# Ports.net
KiCad netlist of a schematic drawn in Altium Designer
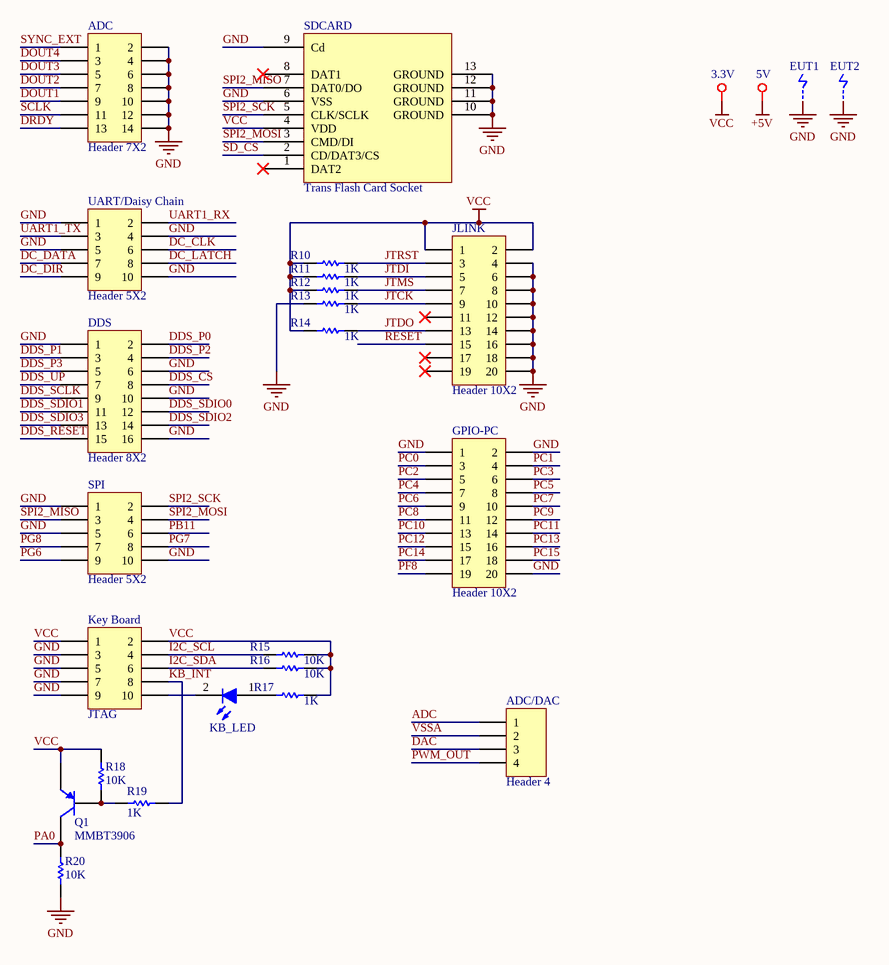
[diagram p0: Ports.SchDoc]

(export (version "E")
  (design (tool "Eeschema 10.0.6"))
  (components
    (comp (ref "3.3V")
      (value "TestPoint")
      (footprint "TestHole")
      (libsource (lib "Slivy's ibrary") (part "TestPoint"))
    )
    (comp (ref "5V")
      (value "TestPoint")
      (footprint "TestHole")
      (libsource (lib "Slivy's ibrary") (part "TestPoint"))
    )
    (comp (ref "ADC")
      (value "Header 7X2")
      (footprint "HEADER7X2")
      (description "Header, 7-Pin, Dual row")
      (fields (field (name "PUBLISHER") "Altium Limited"))
      (libsource (lib "Miscellaneous Connectors") (part "Header 7X2"))
    )
    (comp (ref "ADC/DAC")
      (value "Header 4")
      (footprint "HDR1X4")
      (description "Header, 4-Pin")
      (fields (field (name "PUBLISHER") "Altium Limited"))
      (libsource (lib "Miscellaneous Connectors") (part "Header 4"))
    )
    (comp (ref "DDS")
      (value "Header 8X2")
      (footprint "HEADER8X2")
      (description "Header, 8-Pin, Dual row")
      (fields (field (name "PUBLISHER") "Altium Limited"))
      (libsource (lib "Miscellaneous Connectors") (part "Header 8X2"))
    )
    (comp (ref "EUT1") (value "EUT") (footprint "EUT") (libsource (lib "Slivy's ibrary") (part "EUT")))
    (comp (ref "EUT2") (value "EUT") (footprint "EUT") (libsource (lib "Slivy's ibrary") (part "EUT")))
    (comp (ref "GPIO-PC")
      (value "Header 10X2")
      (footprint "HEADER 10X2")
      (description "Header, 10-Pin, Dual row")
      (fields (field (name "PUBLISHER") "Altium Limited"))
      (libsource (lib "Miscellaneous Connectors") (part "Header 10X2"))
    )
    (comp (ref "JLINK")
      (value "Header 10X2")
      (footprint "HEADER 10X2")
      (description "Header, 10-Pin, Dual row")
      (fields (field (name "PUBLISHER") "Altium Limited"))
      (libsource (lib "Miscellaneous Connectors") (part "Header 10X2"))
    )
    (comp (ref "KB_LED")
      (value "LED-BLUE")
      (footprint "0603LED_BLUE_V")
      (libsource (lib "Slivy's ibrary") (part "LED-BLUE"))
    )
    (comp (ref "Key Board")
      (value "JTAG")
      (footprint "HEADER5X2")
      (description "Header, 5-Pin, Dual row")
      (fields (field (name "MANUFACTURER") "Generic Components"))
      (libsource (lib "Integrated_Library1") (part "Header 5X2"))
    )
    (comp (ref "Q1")
      (value "MMBT3906")
      (footprint "SOT23_M")
      (description "PNP General Purpose Amplifier")
      (fields (field (name "PUBLISHER") "Altium Limited"))
      (libsource (lib "Slivy's ibrary") (part "MMBT3906"))
    )
    (comp (ref "R10")
      (value "1K")
      (footprint "RESC0603(1608)_M")
      (libsource (lib "Slivy's ibrary") (part "RES"))
    )
    (comp (ref "R11")
      (value "1K")
      (footprint "RESC0603(1608)_M")
      (libsource (lib "Slivy's ibrary") (part "RES"))
    )
    (comp (ref "R12")
      (value "1K")
      (footprint "RESC0603(1608)_M")
      (libsource (lib "Slivy's ibrary") (part "RES"))
    )
    (comp (ref "R13")
      (value "1K")
      (footprint "RESC0603(1608)_M")
      (libsource (lib "Slivy's ibrary") (part "RES"))
    )
    (comp (ref "R14")
      (value "1K")
      (footprint "RESC0603(1608)_M")
      (libsource (lib "Slivy's ibrary") (part "RES"))
    )
    (comp (ref "R15")
      (value "10K")
      (footprint "RESC0603(1608)_M")
      (libsource (lib "Slivy's ibrary") (part "RES"))
    )
    (comp (ref "R16")
      (value "10K")
      (footprint "RESC0603(1608)_M")
      (libsource (lib "Slivy's ibrary") (part "RES"))
    )
    (comp (ref "R17")
      (value "1K")
      (footprint "RESC0603(1608)_M")
      (libsource (lib "Slivy's ibrary") (part "RES"))
    )
    (comp (ref "R18")
      (value "10K")
      (footprint "RESC0603(1608)_M")
      (libsource (lib "Slivy's ibrary") (part "RES"))
    )
    (comp (ref "R19")
      (value "1K")
      (footprint "RESC0603(1608)_M")
      (libsource (lib "Slivy's ibrary") (part "RES"))
    )
    (comp (ref "R20")
      (value "10K")
      (footprint "RESC0603(1608)_M")
      (libsource (lib "Slivy's ibrary") (part "RES"))
    )
    (comp (ref "SDCARD")
      (value "Trans Flash Card Socket")
      (footprint "TF Card")
      (libsource (lib "Slivy's ibrary") (part "Trans Flash Card"))
    )
    (comp (ref "SPI")
      (value "Header 5X2")
      (footprint "HEADER5X2")
      (description "Header, 5-Pin, Dual row")
      (fields (field (name "PUBLISHER") "Altium Limited"))
      (libsource (lib "Miscellaneous Connectors") (part "Header 5X2"))
    )
    (comp (ref "UART/Daisy Chain")
      (value "Header 5X2")
      (footprint "HEADER5X2")
      (description "Header, 5-Pin, Dual row")
      (fields (field (name "PUBLISHER") "Altium Limited"))
      (libsource (lib "Miscellaneous Connectors") (part "Header 5X2"))
    )
  )
  (nets
    (net (code "1") (name "+5V") (class "Default")
      (node (ref "5V") (pin "1") (pinfunction "1_1") (pintype "passive"))
    )
    (net (code "2") (name "/ADC") (class "Default")
      (node (ref "ADC/DAC") (pin "1") (pinfunction "1_1") (pintype "passive"))
    )
    (net (code "3") (name "/DAC") (class "Default")
      (node (ref "ADC/DAC") (pin "3") (pinfunction "3_3") (pintype "passive"))
    )
    (net (code "4") (name "/DC_CLK") (class "Default")
      (node (ref "UART/Daisy Chain") (pin "6") (pinfunction "6_6") (pintype "passive"))
    )
    (net (code "5") (name "/DC_DATA") (class "Default")
      (node (ref "UART/Daisy Chain") (pin "7") (pinfunction "7_7") (pintype "passive"))
    )
    (net (code "6") (name "/DC_DIR") (class "Default")
      (node (ref "UART/Daisy Chain") (pin "9") (pinfunction "9_9") (pintype "passive"))
    )
    (net (code "7") (name "/DC_LATCH") (class "Default")
      (node (ref "UART/Daisy Chain") (pin "8") (pinfunction "8_8") (pintype "passive"))
    )
    (net (code "8") (name "/DDS_CS") (class "Default")
      (node (ref "DDS") (pin "8") (pinfunction "8_8") (pintype "passive"))
    )
    (net (code "9") (name "/DDS_P0") (class "Default")
      (node (ref "DDS") (pin "2") (pinfunction "2_2") (pintype "passive"))
    )
    (net (code "10") (name "/DDS_P1") (class "Default")
      (node (ref "DDS") (pin "3") (pinfunction "3_3") (pintype "passive"))
    )
    (net (code "11") (name "/DDS_P2") (class "Default")
      (node (ref "DDS") (pin "4") (pinfunction "4_4") (pintype "passive"))
    )
    (net (code "12") (name "/DDS_P3") (class "Default")
      (node (ref "DDS") (pin "5") (pinfunction "5_5") (pintype "passive"))
    )
    (net (code "13") (name "/DDS_RESET") (class "Default")
      (node (ref "DDS") (pin "15") (pinfunction "15_15") (pintype "passive"))
    )
    (net (code "14") (name "/DDS_SCLK") (class "Default")
      (node (ref "DDS") (pin "9") (pinfunction "9_9") (pintype "passive"))
    )
    (net (code "15") (name "/DDS_SDIO0") (class "Default")
      (node (ref "DDS") (pin "12") (pinfunction "12_12") (pintype "passive"))
    )
    (net (code "16") (name "/DDS_SDIO1") (class "Default")
      (node (ref "DDS") (pin "11") (pinfunction "11_11") (pintype "passive"))
    )
    (net (code "17") (name "/DDS_SDIO2") (class "Default")
      (node (ref "DDS") (pin "14") (pinfunction "14_14") (pintype "passive"))
    )
    (net (code "18") (name "/DDS_SDIO3") (class "Default")
      (node (ref "DDS") (pin "13") (pinfunction "13_13") (pintype "passive"))
    )
    (net (code "19") (name "/DDS_UP") (class "Default")
      (node (ref "DDS") (pin "7") (pinfunction "7_7") (pintype "passive"))
    )
    (net (code "20") (name "/DOUT1") (class "Default")
      (node (ref "ADC") (pin "9") (pinfunction "9_9") (pintype "passive"))
    )
    (net (code "21") (name "/DOUT2") (class "Default")
      (node (ref "ADC") (pin "7") (pinfunction "7_7") (pintype "passive"))
    )
    (net (code "22") (name "/DOUT3") (class "Default")
      (node (ref "ADC") (pin "5") (pinfunction "5_5") (pintype "passive"))
    )
    (net (code "23") (name "/DOUT4") (class "Default")
      (node (ref "ADC") (pin "3") (pinfunction "3_3") (pintype "passive"))
    )
    (net (code "24") (name "/DRDY") (class "Default")
      (node (ref "ADC") (pin "13") (pinfunction "13_13") (pintype "passive"))
    )
    (net (code "25") (name "/I2C_SCL") (class "Default")
      (node (ref "Key Board") (pin "4") (pinfunction "4_4") (pintype "passive"))
      (node (ref "R15") (pin "1") (pinfunction "1_1") (pintype "passive"))
    )
    (net (code "26") (name "/I2C_SDA") (class "Default")
      (node (ref "Key Board") (pin "6") (pinfunction "6_6") (pintype "passive"))
      (node (ref "R16") (pin "1") (pinfunction "1_1") (pintype "passive"))
    )
    (net (code "27") (name "/JTCK") (class "Default")
      (node (ref "JLINK") (pin "9") (pinfunction "9_9") (pintype "passive"))
      (node (ref "R13") (pin "2") (pinfunction "2_2") (pintype "passive"))
    )
    (net (code "28") (name "/JTDI") (class "Default")
      (node (ref "JLINK") (pin "5") (pinfunction "5_5") (pintype "passive"))
      (node (ref "R11") (pin "2") (pinfunction "2_2") (pintype "passive"))
    )
    (net (code "29") (name "/JTDO") (class "Default")
      (node (ref "JLINK") (pin "13") (pinfunction "13_13") (pintype "passive"))
      (node (ref "R14") (pin "2") (pinfunction "2_2") (pintype "passive"))
    )
    (net (code "30") (name "/JTMS") (class "Default")
      (node (ref "JLINK") (pin "7") (pinfunction "7_7") (pintype "passive"))
      (node (ref "R12") (pin "2") (pinfunction "2_2") (pintype "passive"))
    )
    (net (code "31") (name "/JTRST") (class "Default")
      (node (ref "JLINK") (pin "3") (pinfunction "3_3") (pintype "passive"))
      (node (ref "R10") (pin "2") (pinfunction "2_2") (pintype "passive"))
    )
    (net (code "32") (name "/KB_INT") (class "Default")
      (node (ref "Key Board") (pin "8") (pinfunction "8_8") (pintype "passive"))
      (node (ref "R19") (pin "2") (pinfunction "2_2") (pintype "passive"))
    )
    (net (code "33") (name "/PA0") (class "Default")
      (node (ref "Q1") (pin "3") (pinfunction "C_3") (pintype "passive"))
      (node (ref "R20") (pin "2") (pinfunction "2_2") (pintype "passive"))
    )
    (net (code "34") (name "/PB11") (class "Default")
      (node (ref "SPI") (pin "6") (pinfunction "6_6") (pintype "passive"))
    )
    (net (code "35") (name "/PC0") (class "Default")
      (node (ref "GPIO-PC") (pin "3") (pinfunction "3_3") (pintype "passive"))
    )
    (net (code "36") (name "/PC1") (class "Default")
      (node (ref "GPIO-PC") (pin "4") (pinfunction "4_4") (pintype "passive"))
    )
    (net (code "37") (name "/PC2") (class "Default")
      (node (ref "GPIO-PC") (pin "5") (pinfunction "5_5") (pintype "passive"))
    )
    (net (code "38") (name "/PC3") (class "Default")
      (node (ref "GPIO-PC") (pin "6") (pinfunction "6_6") (pintype "passive"))
    )
    (net (code "39") (name "/PC4") (class "Default")
      (node (ref "GPIO-PC") (pin "7") (pinfunction "7_7") (pintype "passive"))
    )
    (net (code "40") (name "/PC5") (class "Default")
      (node (ref "GPIO-PC") (pin "8") (pinfunction "8_8") (pintype "passive"))
    )
    (net (code "41") (name "/PC6") (class "Default")
      (node (ref "GPIO-PC") (pin "9") (pinfunction "9_9") (pintype "passive"))
    )
    (net (code "42") (name "/PC7") (class "Default")
      (node (ref "GPIO-PC") (pin "10") (pinfunction "10_10") (pintype "passive"))
    )
    (net (code "43") (name "/PC8") (class "Default")
      (node (ref "GPIO-PC") (pin "11") (pinfunction "11_11") (pintype "passive"))
    )
    (net (code "44") (name "/PC9") (class "Default")
      (node (ref "GPIO-PC") (pin "12") (pinfunction "12_12") (pintype "passive"))
    )
    (net (code "45") (name "/PC10") (class "Default")
      (node (ref "GPIO-PC") (pin "13") (pinfunction "13_13") (pintype "passive"))
    )
    (net (code "46") (name "/PC11") (class "Default")
      (node (ref "GPIO-PC") (pin "14") (pinfunction "14_14") (pintype "passive"))
    )
    (net (code "47") (name "/PC12") (class "Default")
      (node (ref "GPIO-PC") (pin "15") (pinfunction "15_15") (pintype "passive"))
    )
    (net (code "48") (name "/PC13") (class "Default")
      (node (ref "GPIO-PC") (pin "16") (pinfunction "16_16") (pintype "passive"))
    )
    (net (code "49") (name "/PC14") (class "Default")
      (node (ref "GPIO-PC") (pin "17") (pinfunction "17_17") (pintype "passive"))
    )
    (net (code "50") (name "/PC15") (class "Default")
      (node (ref "GPIO-PC") (pin "18") (pinfunction "18_18") (pintype "passive"))
    )
    (net (code "51") (name "/PF8") (class "Default")
      (node (ref "GPIO-PC") (pin "19") (pinfunction "19_19") (pintype "passive"))
    )
    (net (code "52") (name "/PG6") (class "Default")
      (node (ref "SPI") (pin "9") (pinfunction "9_9") (pintype "passive"))
    )
    (net (code "53") (name "/PG7") (class "Default")
      (node (ref "SPI") (pin "8") (pinfunction "8_8") (pintype "passive"))
    )
    (net (code "54") (name "/PG8") (class "Default")
      (node (ref "SPI") (pin "7") (pinfunction "7_7") (pintype "passive"))
    )
    (net (code "55") (name "/PWM_OUT") (class "Default")
      (node (ref "ADC/DAC") (pin "4") (pinfunction "4_4") (pintype "passive"))
    )
    (net (code "56") (name "/RESET") (class "Default")
      (node (ref "JLINK") (pin "15") (pinfunction "15_15") (pintype "passive"))
    )
    (net (code "57") (name "/SCLK") (class "Default")
      (node (ref "ADC") (pin "11") (pinfunction "11_11") (pintype "passive"))
    )
    (net (code "58") (name "/SD_CS") (class "Default")
      (node (ref "SDCARD") (pin "2") (pinfunction "CD/DAT3/CS_2") (pintype "passive"))
    )
    (net (code "59") (name "/SPI2_MISO") (class "Default")
      (node (ref "SDCARD") (pin "7") (pinfunction "DAT0/DO_7") (pintype "passive"))
      (node (ref "SPI") (pin "3") (pinfunction "3_3") (pintype "passive"))
    )
    (net (code "60") (name "/SPI2_MOSI") (class "Default")
      (node (ref "SDCARD") (pin "3") (pinfunction "CMD/DI_3") (pintype "passive"))
      (node (ref "SPI") (pin "4") (pinfunction "4_4") (pintype "passive"))
    )
    (net (code "61") (name "/SPI2_SCK") (class "Default")
      (node (ref "SDCARD") (pin "5") (pinfunction "CLK/SCLK_5") (pintype "passive"))
      (node (ref "SPI") (pin "2") (pinfunction "2_2") (pintype "passive"))
    )
    (net (code "62") (name "/SYNC_EXT") (class "Default")
      (node (ref "ADC") (pin "1") (pinfunction "1_1") (pintype "passive"))
    )
    (net (code "63") (name "/UART1_RX") (class "Default")
      (node (ref "UART/Daisy Chain") (pin "2") (pinfunction "2_2") (pintype "passive"))
    )
    (net (code "64") (name "/UART1_TX") (class "Default")
      (node (ref "UART/Daisy Chain") (pin "3") (pinfunction "3_3") (pintype "passive"))
    )
    (net (code "65") (name "/VSSA") (class "Default")
      (node (ref "ADC/DAC") (pin "2") (pinfunction "2_2") (pintype "passive"))
    )
    (net (code "66") (name "GND") (class "Default")
      (node (ref "ADC") (pin "10") (pinfunction "10_10") (pintype "passive"))
      (node (ref "ADC") (pin "12") (pinfunction "12_12") (pintype "passive"))
      (node (ref "ADC") (pin "14") (pinfunction "14_14") (pintype "passive"))
      (node (ref "ADC") (pin "2") (pinfunction "2_2") (pintype "passive"))
      (node (ref "ADC") (pin "4") (pinfunction "4_4") (pintype "passive"))
      (node (ref "ADC") (pin "6") (pinfunction "6_6") (pintype "passive"))
      (node (ref "ADC") (pin "8") (pinfunction "8_8") (pintype "passive"))
      (node (ref "DDS") (pin "1") (pinfunction "1_1") (pintype "passive"))
      (node (ref "DDS") (pin "10") (pinfunction "10_10") (pintype "passive"))
      (node (ref "DDS") (pin "16") (pinfunction "16_16") (pintype "passive"))
      (node (ref "DDS") (pin "6") (pinfunction "6_6") (pintype "passive"))
      (node (ref "EUT1") (pin "2") (pinfunction "2_2") (pintype "passive"))
      (node (ref "EUT2") (pin "2") (pinfunction "2_2") (pintype "passive"))
      (node (ref "GPIO-PC") (pin "1") (pinfunction "1_1") (pintype "passive"))
      (node (ref "GPIO-PC") (pin "2") (pinfunction "2_2") (pintype "passive"))
      (node (ref "GPIO-PC") (pin "20") (pinfunction "20_20") (pintype "passive"))
      (node (ref "JLINK") (pin "10") (pinfunction "10_10") (pintype "passive"))
      (node (ref "JLINK") (pin "12") (pinfunction "12_12") (pintype "passive"))
      (node (ref "JLINK") (pin "14") (pinfunction "14_14") (pintype "passive"))
      (node (ref "JLINK") (pin "16") (pinfunction "16_16") (pintype "passive"))
      (node (ref "JLINK") (pin "18") (pinfunction "18_18") (pintype "passive"))
      (node (ref "JLINK") (pin "20") (pinfunction "20_20") (pintype "passive"))
      (node (ref "JLINK") (pin "4") (pinfunction "4_4") (pintype "passive"))
      (node (ref "JLINK") (pin "6") (pinfunction "6_6") (pintype "passive"))
      (node (ref "JLINK") (pin "8") (pinfunction "8_8") (pintype "passive"))
      (node (ref "Key Board") (pin "3") (pinfunction "3_3") (pintype "passive"))
      (node (ref "Key Board") (pin "5") (pinfunction "5_5") (pintype "passive"))
      (node (ref "Key Board") (pin "7") (pinfunction "7_7") (pintype "passive"))
      (node (ref "Key Board") (pin "9") (pinfunction "9_9") (pintype "passive"))
      (node (ref "R13") (pin "1") (pinfunction "1_1") (pintype "passive"))
      (node (ref "R20") (pin "1") (pinfunction "1_1") (pintype "passive"))
      (node (ref "SDCARD") (pin "10") (pinfunction "GROUND_10") (pintype "passive"))
      (node (ref "SDCARD") (pin "11") (pinfunction "GROUND_11") (pintype "passive"))
      (node (ref "SDCARD") (pin "12") (pinfunction "GROUND_12") (pintype "passive"))
      (node (ref "SDCARD") (pin "13") (pinfunction "GROUND_13") (pintype "passive"))
      (node (ref "SDCARD") (pin "6") (pinfunction "VSS_6") (pintype "passive"))
      (node (ref "SDCARD") (pin "9") (pinfunction "Cd_9") (pintype "passive"))
      (node (ref "SPI") (pin "1") (pinfunction "1_1") (pintype "passive"))
      (node (ref "SPI") (pin "10") (pinfunction "10_10") (pintype "passive"))
      (node (ref "SPI") (pin "5") (pinfunction "5_5") (pintype "passive"))
      (node (ref "UART/Daisy Chain") (pin "1") (pinfunction "1_1") (pintype "passive"))
      (node (ref "UART/Daisy Chain") (pin "10") (pinfunction "10_10") (pintype "passive"))
      (node (ref "UART/Daisy Chain") (pin "4") (pinfunction "4_4") (pintype "passive"))
      (node (ref "UART/Daisy Chain") (pin "5") (pinfunction "5_5") (pintype "passive"))
    )
    (net (code "67") (name "Net-(KB_LED-A)") (class "Default")
      (node (ref "KB_LED") (pin "1") (pinfunction "A_1") (pintype "passive"))
      (node (ref "R17") (pin "1") (pinfunction "1_1") (pintype "passive"))
    )
    (net (code "68") (name "Net-(KB_LED-K)") (class "Default")
      (node (ref "KB_LED") (pin "2") (pinfunction "K_2") (pintype "passive"))
      (node (ref "Key Board") (pin "10") (pinfunction "10_10") (pintype "passive"))
    )
    (net (code "69") (name "Net-(Q1-B)") (class "Default")
      (node (ref "Q1") (pin "1") (pinfunction "B_1") (pintype "passive"))
      (node (ref "R18") (pin "1") (pinfunction "1_1") (pintype "passive"))
      (node (ref "R19") (pin "1") (pinfunction "1_1") (pintype "passive"))
    )
    (net (code "70") (name "VCC") (class "Default")
      (node (ref "3.3V") (pin "1") (pinfunction "1_1") (pintype "passive"))
      (node (ref "JLINK") (pin "1") (pinfunction "1_1") (pintype "passive"))
      (node (ref "JLINK") (pin "2") (pinfunction "2_2") (pintype "passive"))
      (node (ref "Key Board") (pin "1") (pinfunction "1_1") (pintype "passive"))
      (node (ref "Key Board") (pin "2") (pinfunction "2_2") (pintype "passive"))
      (node (ref "Q1") (pin "2") (pinfunction "E_2") (pintype "passive"))
      (node (ref "R10") (pin "1") (pinfunction "1_1") (pintype "passive"))
      (node (ref "R11") (pin "1") (pinfunction "1_1") (pintype "passive"))
      (node (ref "R12") (pin "1") (pinfunction "1_1") (pintype "passive"))
      (node (ref "R14") (pin "1") (pinfunction "1_1") (pintype "passive"))
      (node (ref "R15") (pin "2") (pinfunction "2_2") (pintype "passive"))
      (node (ref "R16") (pin "2") (pinfunction "2_2") (pintype "passive"))
      (node (ref "R17") (pin "2") (pinfunction "2_2") (pintype "passive"))
      (node (ref "R18") (pin "2") (pinfunction "2_2") (pintype "passive"))
      (node (ref "SDCARD") (pin "4") (pinfunction "VDD_4") (pintype "passive"))
    )
    (net (code "71") (name "unconnected-(JLINK-Pad11)") (class "Default")
      (node (ref "JLINK") (pin "11") (pinfunction "11_11") (pintype "passive+no_connect"))
    )
    (net (code "72") (name "unconnected-(JLINK-Pad17)") (class "Default")
      (node (ref "JLINK") (pin "17") (pinfunction "17_17") (pintype "passive+no_connect"))
    )
    (net (code "73") (name "unconnected-(JLINK-Pad19)") (class "Default")
      (node (ref "JLINK") (pin "19") (pinfunction "19_19") (pintype "passive+no_connect"))
    )
    (net (code "74") (name "unconnected-(SDCARD-DAT1-Pad8)") (class "Default")
      (node (ref "SDCARD") (pin "8") (pinfunction "DAT1_8") (pintype "passive+no_connect"))
    )
    (net (code "75") (name "unconnected-(SDCARD-DAT2-Pad1)") (class "Default")
      (node (ref "SDCARD") (pin "1") (pinfunction "DAT2_1") (pintype "passive+no_connect"))
    )
  )
)
